# Esq.net
KiCad netlist of a schematic drawn in Altium Designer
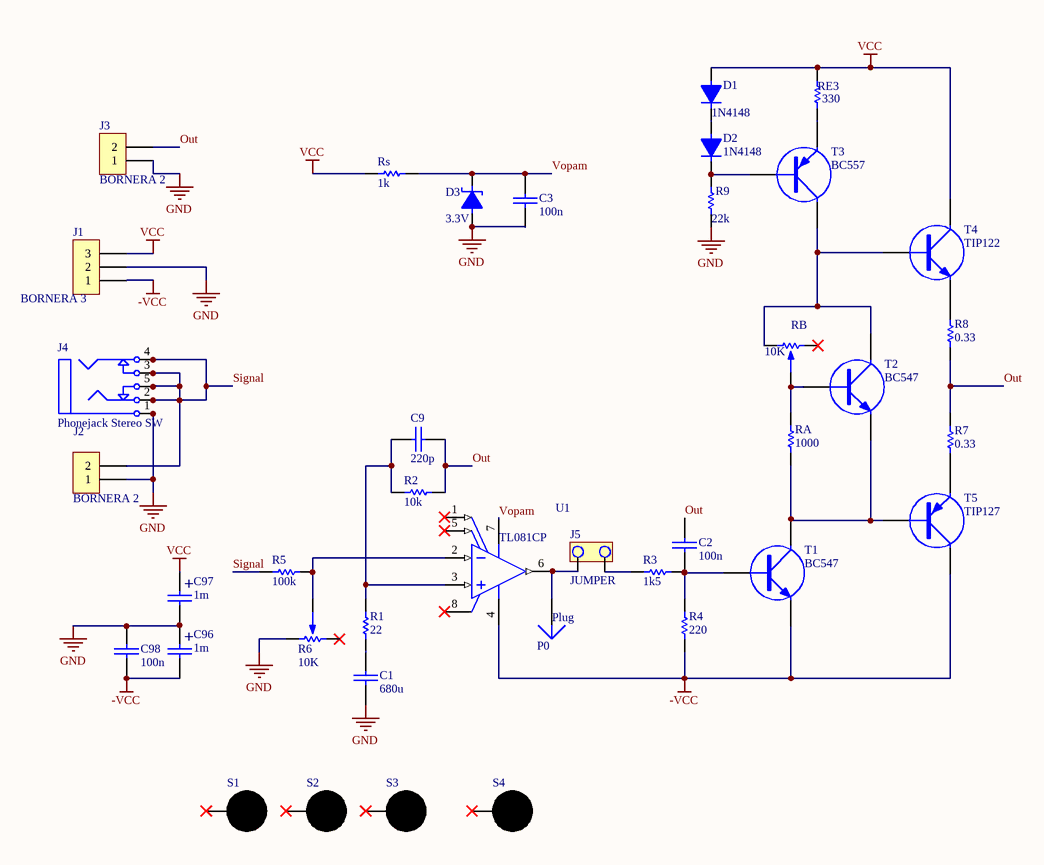
[diagram p0: Esq.SchDoc]

(export (version "E")
  (design (tool "Eeschema 10.0.6"))
  (components
    (comp (ref "C1") (value "680u") (footprint "CAP200") (libsource (lib "LIB PIO IX") (part "CAP")))
    (comp (ref "C2") (value "100n") (footprint "CAP200") (libsource (lib "LIB PIO IX") (part "CAP")))
    (comp (ref "C3") (value "100n") (footprint "CAP200") (libsource (lib "LIB PIO IX") (part "CAP")))
    (comp (ref "C9") (value "220p") (footprint "CAP200") (libsource (lib "LIB PIO IX") (part "CAP")))
    (comp (ref "C96") (value "1m") (footprint "CAP200RP2") (libsource (lib "LIB PIO IX") (part "CAPPOL")))
    (comp (ref "C97") (value "1m") (footprint "CAP200RP2") (libsource (lib "LIB PIO IX") (part "CAPPOL")))
    (comp (ref "C98") (value "100n") (footprint "CAP200") (libsource (lib "LIB PIO IX") (part "CAP")))
    (comp (ref "D1") (value "1N4148") (footprint "DO41") (libsource (lib "LIB PIO IX") (part "DIODO")))
    (comp (ref "D2") (value "1N4148") (footprint "DO41") (libsource (lib "LIB PIO IX") (part "DIODO")))
    (comp (ref "D3") (value "3.3V") (footprint "DO41") (libsource (lib "LIB PIO IX") (part "DIODO ZENER")))
    (comp (ref "J1")
      (value "BORNERA 3")
      (footprint "BORNERA3")
      (libsource (lib "LIB PIO IX") (part "BORNERA 3"))
    )
    (comp (ref "J2")
      (value "BORNERA 2")
      (footprint "BORNERA2")
      (libsource (lib "LIB PIO IX") (part "BORNERA 2"))
    )
    (comp (ref "J3")
      (value "BORNERA 2")
      (footprint "BORNERA2")
      (libsource (lib "LIB PIO IX") (part "BORNERA 2"))
    )
    (comp (ref "J4")
      (value "Phonejack Stereo SW")
      (footprint "ST-3150-5N")
      (description "3-Conductor Jack with 2 break contacts (normals) and 2 auxiliary make contacts")
      (fields (field (name "PUBLISHER") "Altium Limited"))
      (libsource (lib "Miscellaneous Connectors") (part "Phonejack Stereo SW"))
    )
    (comp (ref "J5") (value "JUMPER") (footprint "JUMPER2") (libsource (lib "LIB PIO IX") (part "JUMPER")))
    (comp (ref "P0")
      (value "Plug")
      (footprint "PIN1")
      (fields (field (name "PUBLISHER") "Altium Limited"))
      (libsource (lib "Miscellaneous Connectors") (part "Plug"))
    )
    (comp (ref "R1") (value "22") (footprint "RES400") (libsource (lib "LIB PIO IX") (part "RES")))
    (comp (ref "R2") (value "10k") (footprint "RES400") (libsource (lib "LIB PIO IX") (part "RES")))
    (comp (ref "R3") (value "1k5") (footprint "RES400") (libsource (lib "LIB PIO IX") (part "RES")))
    (comp (ref "R4") (value "220") (footprint "RES400") (libsource (lib "LIB PIO IX") (part "RES")))
    (comp (ref "R5") (value "100k") (footprint "RES400") (libsource (lib "LIB PIO IX") (part "RES")))
    (comp (ref "R6") (value "10K") (footprint "PRESET V") (libsource (lib "LIB PIO IX") (part "PRESET")))
    (comp (ref "R7") (value "0.33") (footprint "RES600") (libsource (lib "LIB PIO IX") (part "RES")))
    (comp (ref "R8") (value "0.33") (footprint "RES600") (libsource (lib "LIB PIO IX") (part "RES")))
    (comp (ref "R9") (value "22k") (footprint "RES400") (libsource (lib "LIB PIO IX") (part "RES")))
    (comp (ref "RA") (value "1000") (footprint "RES400") (libsource (lib "LIB PIO IX") (part "RES")))
    (comp (ref "RB") (value "10K") (footprint "PRESET V") (libsource (lib "LIB PIO IX") (part "PRESET")))
    (comp (ref "RE3") (value "330") (footprint "RES400") (libsource (lib "LIB PIO IX") (part "RES")))
    (comp (ref "Rs") (value "1k") (footprint "RES600") (libsource (lib "LIB PIO IX") (part "RES")))
    (comp (ref "S1")
      (value "~")
      (footprint "SUJECION (5.00MM - 3.50MM)")
      (libsource (lib "LIB2013") (part "SUJECION"))
    )
    (comp (ref "S2")
      (value "~")
      (footprint "SUJECION (5.00MM - 3.50MM)")
      (libsource (lib "LIB2013") (part "SUJECION"))
    )
    (comp (ref "S3")
      (value "~")
      (footprint "SUJECION (5.00MM - 3.50MM)")
      (libsource (lib "LIB2013") (part "SUJECION"))
    )
    (comp (ref "S4")
      (value "~")
      (footprint "SUJECION (5.00MM - 3.50MM)")
      (libsource (lib "LIB2013") (part "SUJECION"))
    )
    (comp (ref "T1")
      (value "BC547")
      (footprint "TO92")
      (libsource (lib "LIB PIO IX") (part "TRANSISTOR NPN"))
    )
    (comp (ref "T2")
      (value "BC547")
      (footprint "TO92")
      (libsource (lib "LIB PIO IX") (part "TRANSISTOR NPN"))
    )
    (comp (ref "T3")
      (value "BC557")
      (footprint "TO92")
      (libsource (lib "LIB PIO IX") (part "TRANSISTOR PNP"))
    )
    (comp (ref "T4")
      (value "TIP122")
      (footprint "TO-220 V")
      (libsource (lib "LIB PIO IX") (part "TRANSISTOR NPN"))
    )
    (comp (ref "T5")
      (value "TIP127")
      (footprint "TO-220 V")
      (libsource (lib "LIB PIO IX") (part "TRANSISTOR PNP"))
    )
    (comp (ref "U1")
      (value "TL081CP")
      (footprint "P0008A")
      (description "JFET-Input Operational Amplifier, 7 to 36 V, 0 to 70 degC, 8-pin DIP (P8), Pb-Free (RoHS)")
      (fields (field (name "MANUFACTURER") "Texas Instruments"))
      (libsource (lib "Altium Content Vault") (part "TI-AMP-S5-2-8"))
    )
  )
  (nets
    (net (code "1") (name "-VCC") (class "Default")
      (node (ref "C96") (pin "2") (pinfunction "2_2") (pintype "passive"))
      (node (ref "C98") (pin "1") (pinfunction "1_1") (pintype "passive"))
      (node (ref "J1") (pin "1") (pinfunction "1_1") (pintype "passive"))
      (node (ref "R4") (pin "1") (pinfunction "1_1") (pintype "passive"))
      (node (ref "T1") (pin "3") (pinfunction "E_3") (pintype "passive"))
      (node (ref "T5") (pin "2") (pinfunction "C_2") (pintype "passive"))
      (node (ref "U1") (pin "4") (pinfunction "VCC-_4") (pintype "power_in"))
    )
    (net (code "2") (name "/Out") (class "Default")
      (node (ref "C2") (pin "2") (pinfunction "2_2") (pintype "passive"))
      (node (ref "C9") (pin "2") (pinfunction "2_2") (pintype "passive"))
      (node (ref "J3") (pin "2") (pinfunction "2_2") (pintype "passive"))
      (node (ref "R2") (pin "2") (pinfunction "2_2") (pintype "passive"))
      (node (ref "R7") (pin "2") (pinfunction "2_2") (pintype "passive"))
      (node (ref "R8") (pin "1") (pinfunction "1_1") (pintype "passive"))
    )
    (net (code "3") (name "/Signal") (class "Default")
      (node (ref "J2") (pin "2") (pinfunction "2_2") (pintype "passive"))
      (node (ref "J4") (pin "2") (pinfunction "2_2") (pintype "passive"))
      (node (ref "J4") (pin "2A") (pinfunction "2A_2A") (pintype "passive"))
      (node (ref "J4") (pin "2B") (pinfunction "2B_2B") (pintype "passive"))
      (node (ref "J4") (pin "3") (pinfunction "3_3") (pintype "passive"))
      (node (ref "J4") (pin "3A") (pinfunction "3A_3A") (pintype "passive"))
      (node (ref "J4") (pin "3B") (pinfunction "3B_3B") (pintype "passive"))
      (node (ref "J4") (pin "4") (pinfunction "4_4") (pintype "passive"))
      (node (ref "J4") (pin "4A") (pinfunction "4A_4A") (pintype "passive"))
      (node (ref "J4") (pin "4B") (pinfunction "4B_4B") (pintype "passive"))
      (node (ref "J4") (pin "5") (pinfunction "5_5") (pintype "passive"))
      (node (ref "J4") (pin "5A") (pinfunction "5A_5A") (pintype "passive"))
      (node (ref "J4") (pin "5B") (pinfunction "5B_5B") (pintype "passive"))
      (node (ref "R5") (pin "2") (pinfunction "2_2") (pintype "passive"))
    )
    (net (code "4") (name "/Vopam") (class "Default")
      (node (ref "C3") (pin "2") (pinfunction "2_2") (pintype "passive"))
      (node (ref "D3") (pin "2") (pinfunction "2_2") (pintype "passive"))
      (node (ref "Rs") (pin "2") (pinfunction "2_2") (pintype "passive"))
      (node (ref "U1") (pin "7") (pinfunction "VCC+_7") (pintype "power_in"))
    )
    (net (code "5") (name "GND") (class "Default")
      (node (ref "C1") (pin "1") (pinfunction "1_1") (pintype "passive"))
      (node (ref "C3") (pin "1") (pinfunction "1_1") (pintype "passive"))
      (node (ref "C96") (pin "1") (pinfunction "1_1") (pintype "passive"))
      (node (ref "C97") (pin "2") (pinfunction "2_2") (pintype "passive"))
      (node (ref "C98") (pin "2") (pinfunction "2_2") (pintype "passive"))
      (node (ref "D3") (pin "1") (pinfunction "1_1") (pintype "passive"))
      (node (ref "J1") (pin "2") (pinfunction "2_2") (pintype "passive"))
      (node (ref "J2") (pin "1") (pinfunction "1_1") (pintype "passive"))
      (node (ref "J3") (pin "1") (pinfunction "1_1") (pintype "passive"))
      (node (ref "J4") (pin "1") (pinfunction "1_1") (pintype "passive"))
      (node (ref "J4") (pin "1A") (pinfunction "1A_1A") (pintype "passive"))
      (node (ref "J4") (pin "1B") (pinfunction "1B_1B") (pintype "passive"))
      (node (ref "R6") (pin "1") (pinfunction "1_1") (pintype "passive"))
      (node (ref "R9") (pin "1") (pinfunction "1_1") (pintype "passive"))
    )
    (net (code "6") (name "Net-(C1-Pad2)") (class "Default")
      (node (ref "C1") (pin "2") (pinfunction "2_2") (pintype "passive"))
      (node (ref "R1") (pin "1") (pinfunction "1_1") (pintype "passive"))
    )
    (net (code "7") (name "Net-(D1-Pad2)") (class "Default")
      (node (ref "D1") (pin "2") (pinfunction "2_2") (pintype "passive"))
      (node (ref "D2") (pin "1") (pinfunction "1_1") (pintype "passive"))
    )
    (net (code "8") (name "Net-(J5-Pad1)") (class "Default")
      (node (ref "J5") (pin "1") (pinfunction "1_1") (pintype "passive"))
      (node (ref "R3") (pin "1") (pinfunction "1_1") (pintype "passive"))
    )
    (net (code "9") (name "Net-(T1-B)") (class "Default")
      (node (ref "C2") (pin "1") (pinfunction "1_1") (pintype "passive"))
      (node (ref "R3") (pin "2") (pinfunction "2_2") (pintype "passive"))
      (node (ref "R4") (pin "2") (pinfunction "2_2") (pintype "passive"))
      (node (ref "T1") (pin "1") (pinfunction "B_1") (pintype "passive"))
    )
    (net (code "10") (name "Net-(T1-C)") (class "Default")
      (node (ref "RA") (pin "1") (pinfunction "1_1") (pintype "passive"))
      (node (ref "T1") (pin "2") (pinfunction "C_2") (pintype "passive"))
      (node (ref "T2") (pin "3") (pinfunction "E_3") (pintype "passive"))
      (node (ref "T5") (pin "1") (pinfunction "B_1") (pintype "passive"))
    )
    (net (code "11") (name "Net-(T2-B)") (class "Default")
      (node (ref "RA") (pin "2") (pinfunction "2_2") (pintype "passive"))
      (node (ref "RB") (pin "2") (pinfunction "2_2") (pintype "passive"))
      (node (ref "T2") (pin "1") (pinfunction "B_1") (pintype "passive"))
    )
    (net (code "12") (name "Net-(T2-C)") (class "Default")
      (node (ref "RB") (pin "3") (pinfunction "3_3") (pintype "passive"))
      (node (ref "T2") (pin "2") (pinfunction "C_2") (pintype "passive"))
      (node (ref "T3") (pin "2") (pinfunction "C_2") (pintype "passive"))
      (node (ref "T4") (pin "1") (pinfunction "B_1") (pintype "passive"))
    )
    (net (code "13") (name "Net-(T3-B)") (class "Default")
      (node (ref "D2") (pin "2") (pinfunction "2_2") (pintype "passive"))
      (node (ref "R9") (pin "2") (pinfunction "2_2") (pintype "passive"))
      (node (ref "T3") (pin "1") (pinfunction "B_1") (pintype "passive"))
    )
    (net (code "14") (name "Net-(T3-E)") (class "Default")
      (node (ref "RE3") (pin "1") (pinfunction "1_1") (pintype "passive"))
      (node (ref "T3") (pin "3") (pinfunction "E_3") (pintype "passive"))
    )
    (net (code "15") (name "Net-(T4-E)") (class "Default")
      (node (ref "R8") (pin "2") (pinfunction "2_2") (pintype "passive"))
      (node (ref "T4") (pin "3") (pinfunction "E_3") (pintype "passive"))
    )
    (net (code "16") (name "Net-(T5-E)") (class "Default")
      (node (ref "R7") (pin "1") (pinfunction "1_1") (pintype "passive"))
      (node (ref "T5") (pin "3") (pinfunction "E_3") (pintype "passive"))
    )
    (net (code "17") (name "Net-(U1-IN+)") (class "Default")
      (node (ref "C9") (pin "1") (pinfunction "1_1") (pintype "passive"))
      (node (ref "R1") (pin "2") (pinfunction "2_2") (pintype "passive"))
      (node (ref "R2") (pin "1") (pinfunction "1_1") (pintype "passive"))
      (node (ref "U1") (pin "3") (pinfunction "IN+_3") (pintype "input"))
    )
    (net (code "18") (name "Net-(U1-IN-)") (class "Default")
      (node (ref "R5") (pin "1") (pinfunction "1_1") (pintype "passive"))
      (node (ref "R6") (pin "2") (pinfunction "2_2") (pintype "passive"))
      (node (ref "U1") (pin "2") (pinfunction "IN-_2") (pintype "input"))
    )
    (net (code "19") (name "Net-(U1-OUT)") (class "Default")
      (node (ref "J5") (pin "2") (pinfunction "2_2") (pintype "passive"))
      (node (ref "P0") (pin "1") (pinfunction "1_1") (pintype "passive"))
      (node (ref "U1") (pin "6") (pinfunction "OUT_6") (pintype "output"))
    )
    (net (code "20") (name "VCC") (class "Default")
      (node (ref "C97") (pin "1") (pinfunction "1_1") (pintype "passive"))
      (node (ref "D1") (pin "1") (pinfunction "1_1") (pintype "passive"))
      (node (ref "J1") (pin "3") (pinfunction "3_3") (pintype "passive"))
      (node (ref "RE3") (pin "2") (pinfunction "2_2") (pintype "passive"))
      (node (ref "Rs") (pin "1") (pinfunction "1_1") (pintype "passive"))
      (node (ref "T4") (pin "2") (pinfunction "C_2") (pintype "passive"))
    )
    (net (code "21") (name "unconnected-(R6-Pad3)") (class "Default")
      (node (ref "R6") (pin "3") (pinfunction "3_3") (pintype "passive+no_connect"))
    )
    (net (code "22") (name "unconnected-(RB-Pad1)") (class "Default")
      (node (ref "RB") (pin "1") (pinfunction "1_1") (pintype "passive+no_connect"))
    )
    (net (code "23") (name "unconnected-(S1-Pad1)") (class "Default")
      (node (ref "S1") (pin "1") (pinfunction "1_1") (pintype "passive+no_connect"))
    )
    (net (code "24") (name "unconnected-(S2-Pad1)") (class "Default")
      (node (ref "S2") (pin "1") (pinfunction "1_1") (pintype "passive+no_connect"))
    )
    (net (code "25") (name "unconnected-(S3-Pad1)") (class "Default")
      (node (ref "S3") (pin "1") (pinfunction "1_1") (pintype "passive+no_connect"))
    )
    (net (code "26") (name "unconnected-(S4-Pad1)") (class "Default")
      (node (ref "S4") (pin "1") (pinfunction "1_1") (pintype "passive+no_connect"))
    )
    (net (code "27") (name "unconnected-(U1-NC-Pad8)") (class "Default")
      (node (ref "U1") (pin "8") (pinfunction "NC_8") (pintype "passive+no_connect"))
    )
    (net (code "28") (name "unconnected-(U1-OFFSET_N1-Pad1)") (class "Default")
      (node (ref "U1") (pin "1") (pinfunction "OFFSET_N1_1") (pintype "input+no_connect"))
    )
    (net (code "29") (name "unconnected-(U1-OFFSET_N2-Pad5)") (class "Default")
      (node (ref "U1") (pin "5") (pinfunction "OFFSET_N2_5") (pintype "input+no_connect"))
    )
  )
)
